# mpg-200-prototype_v3-with-logo-merged.net
KiCad netlist of a schematic drawn in EAGLE
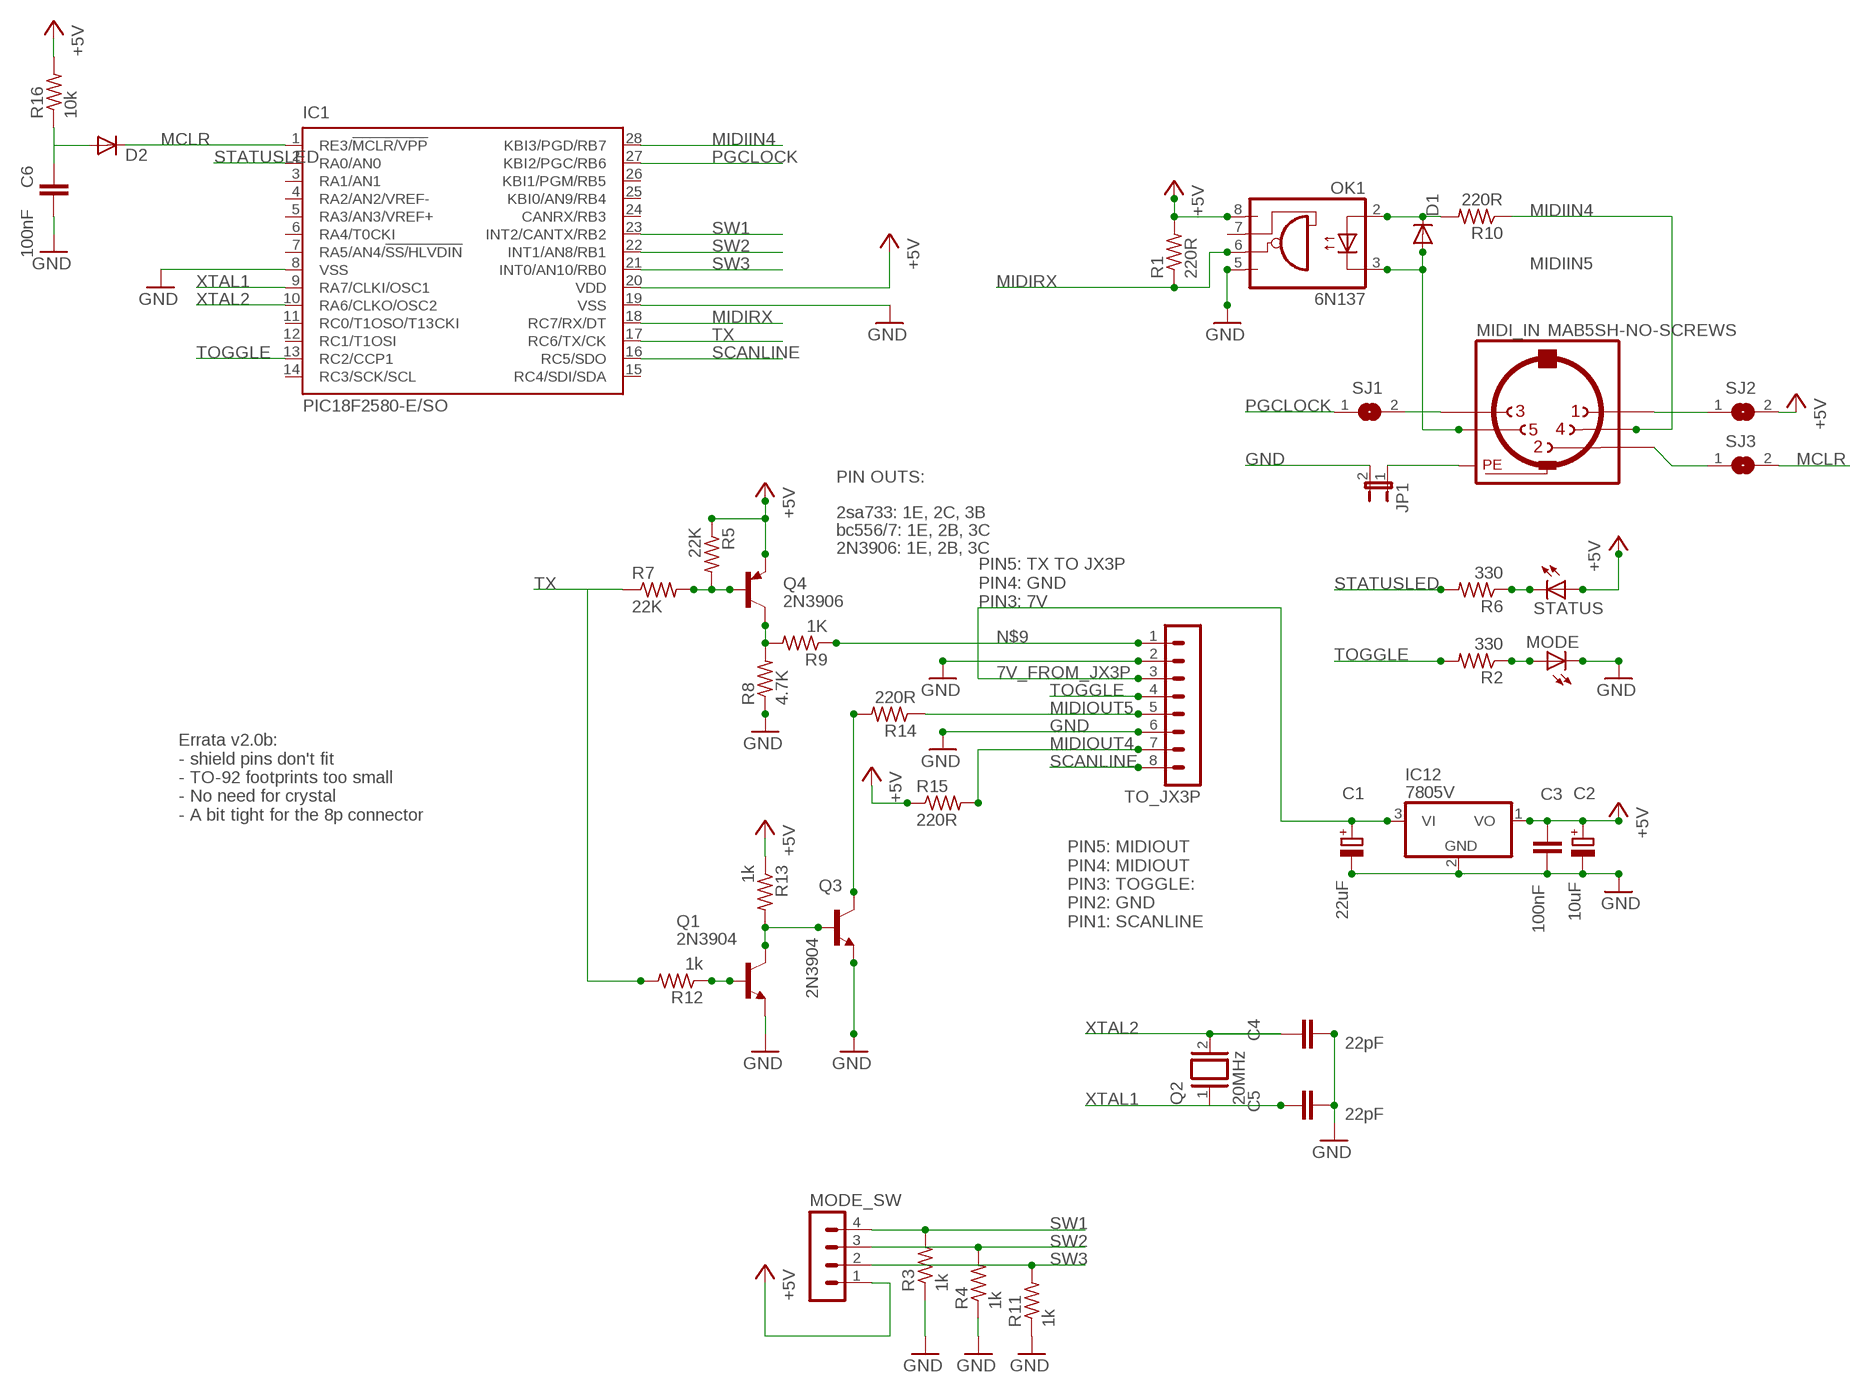
[diagram p0: schematic, sheet 1]

(export (version "E")
  (design (tool "Eeschema 10.0.6"))
  (components
    (comp (ref "C1")
      (value "22uF")
      (footprint "eagle-import:E2,5-5")
      (libsource (lib "eagle-import") (part "CPOL-EUE2.5-5"))
    )
    (comp (ref "C2")
      (value "10uF")
      (footprint "eagle-import:E2,5-5")
      (libsource (lib "eagle-import") (part "CPOL-EUE2.5-5"))
    )
    (comp (ref "C3")
      (value "100nF")
      (footprint "eagle-import:C0805")
      (libsource (lib "eagle-import") (part "C-EUC0805"))
    )
    (comp (ref "C4")
      (value "22pF")
      (footprint "eagle-import:C0805")
      (libsource (lib "eagle-import") (part "C-EUC0805"))
    )
    (comp (ref "C5")
      (value "22pF")
      (footprint "eagle-import:C0805")
      (libsource (lib "eagle-import") (part "C-EUC0805"))
    )
    (comp (ref "C6")
      (value "100nF")
      (footprint "eagle-import:C0805")
      (libsource (lib "eagle-import") (part "C-EUC0805"))
    )
    (comp (ref "D1")
      (value "DIODE-SOD80C")
      (footprint "eagle-import:SOD80C")
      (libsource (lib "eagle-import") (part "DIODE-SOD80C"))
    )
    (comp (ref "D2")
      (value "DIODE-SOD80C")
      (footprint "eagle-import:SOD80C")
      (libsource (lib "eagle-import") (part "DIODE-SOD80C"))
    )
    (comp (ref "IC1")
      (value "PIC18F2580-E/SO")
      (footprint "eagle-import:SO28W")
      (fields (field (name "MF") "MICROCHIP") (field (name "MPN") "PIC18F2580-I/SO"))
      (libsource (lib "eagle-import") (part "PIC18F280-E/SO5"))
    )
    (comp (ref "IC12")
      (value "7805V")
      (footprint "eagle-import:TO92")
      (libsource (lib "eagle-import") (part "78L05"))
    )
    (comp (ref "JP1")
      (value "JP1E")
      (footprint "eagle-import:JP1")
      (libsource (lib "eagle-import") (part "JP1E"))
    )
    (comp (ref "MIDI_IN")
      (value "MAB5SH-NO-SCREWS")
      (footprint "eagle-import:MAB5SH-NO-SCREWS")
      (libsource (lib "eagle-import") (part "MAB5SH-NO-SCREWS"))
    )
    (comp (ref "MODE")
      (value "LED3MM")
      (footprint "eagle-import:LED3MM")
      (libsource (lib "eagle-import") (part "LED3MM"))
    )
    (comp (ref "MODE_SW")
      (value "MA04-1")
      (footprint "eagle-import:MA04-1")
      (libsource (lib "eagle-import") (part "MA04-1"))
    )
    (comp (ref "OK1")
      (value "6N137")
      (footprint "eagle-import:DIL08")
      (libsource (lib "eagle-import") (part "6N137"))
    )
    (comp (ref "Q1")
      (value "2N3904")
      (footprint "eagle-import:TO92")
      (libsource (lib "eagle-import") (part "2N3904"))
    )
    (comp (ref "Q2")
      (value "20MHz")
      (footprint "eagle-import:QS")
      (libsource (lib "eagle-import") (part "XTAL/S"))
    )
    (comp (ref "Q3")
      (value "2N3904")
      (footprint "eagle-import:TO92")
      (libsource (lib "eagle-import") (part "2N3904"))
    )
    (comp (ref "Q4")
      (value "2N3906")
      (footprint "eagle-import:TO92")
      (libsource (lib "eagle-import") (part "2N3906"))
    )
    (comp (ref "R1")
      (value "220R")
      (footprint "eagle-import:R0805")
      (libsource (lib "eagle-import") (part "R-US_R0805"))
    )
    (comp (ref "R2")
      (value "330")
      (footprint "eagle-import:R0805")
      (libsource (lib "eagle-import") (part "R-US_R0805"))
    )
    (comp (ref "R3")
      (value "1k")
      (footprint "eagle-import:R0805")
      (libsource (lib "eagle-import") (part "R-US_R0805"))
    )
    (comp (ref "R4")
      (value "1k")
      (footprint "eagle-import:R0805")
      (libsource (lib "eagle-import") (part "R-US_R0805"))
    )
    (comp (ref "R5")
      (value "22K")
      (footprint "eagle-import:R0805")
      (libsource (lib "eagle-import") (part "R-US_R0805"))
    )
    (comp (ref "R6")
      (value "330")
      (footprint "eagle-import:R0805")
      (libsource (lib "eagle-import") (part "R-US_R0805"))
    )
    (comp (ref "R7")
      (value "22K")
      (footprint "eagle-import:R0805")
      (libsource (lib "eagle-import") (part "R-US_R0805"))
    )
    (comp (ref "R8")
      (value "4.7K")
      (footprint "eagle-import:R0805")
      (libsource (lib "eagle-import") (part "R-US_R0805"))
    )
    (comp (ref "R9")
      (value "1K")
      (footprint "eagle-import:R0805")
      (libsource (lib "eagle-import") (part "R-US_R0805"))
    )
    (comp (ref "R10")
      (value "220R")
      (footprint "eagle-import:R0805")
      (libsource (lib "eagle-import") (part "R-US_R0805"))
    )
    (comp (ref "R11")
      (value "1k")
      (footprint "eagle-import:R0805")
      (libsource (lib "eagle-import") (part "R-US_R0805"))
    )
    (comp (ref "R12")
      (value "1k")
      (footprint "eagle-import:R0805")
      (libsource (lib "eagle-import") (part "R-US_R0805"))
    )
    (comp (ref "R13")
      (value "1k")
      (footprint "eagle-import:R0805")
      (libsource (lib "eagle-import") (part "R-US_R0805"))
    )
    (comp (ref "R14")
      (value "220R")
      (footprint "eagle-import:R0805")
      (libsource (lib "eagle-import") (part "R-US_R0805"))
    )
    (comp (ref "R15")
      (value "220R")
      (footprint "eagle-import:R0805")
      (libsource (lib "eagle-import") (part "R-US_R0805"))
    )
    (comp (ref "R16")
      (value "10k")
      (footprint "eagle-import:R0805")
      (libsource (lib "eagle-import") (part "R-US_R0805"))
    )
    (comp (ref "SJ1") (value "SJ") (footprint "eagle-import:SJ") (libsource (lib "eagle-import") (part "SJ")))
    (comp (ref "SJ2") (value "SJ") (footprint "eagle-import:SJ") (libsource (lib "eagle-import") (part "SJ")))
    (comp (ref "SJ3") (value "SJ") (footprint "eagle-import:SJ") (libsource (lib "eagle-import") (part "SJ")))
    (comp (ref "STATUS")
      (value "LED3MM")
      (footprint "eagle-import:LED3MM")
      (libsource (lib "eagle-import") (part "LED3MM"))
    )
    (comp (ref "TO_JX3P")
      (value "MA08-1")
      (footprint "eagle-import:MA08-1")
      (libsource (lib "eagle-import") (part "MA08-1"))
    )
  )
  (nets
    (net (code "1") (name "+5V") (class "Default")
      (node (ref "C2") (pin "+") (pinfunction "+_+") (pintype "passive"))
      (node (ref "C3") (pin "1") (pinfunction "1_1") (pintype "passive"))
      (node (ref "IC1") (pin "20") (pinfunction "VDD_20") (pintype "power_in"))
      (node (ref "IC12") (pin "1") (pinfunction "VO_1") (pintype "passive"))
      (node (ref "MODE_SW") (pin "1") (pinfunction "1_1") (pintype "passive"))
      (node (ref "OK1") (pin "8") (pinfunction "VCC_8") (pintype "passive"))
      (node (ref "Q4") (pin "1") (pinfunction "E_1") (pintype "passive"))
      (node (ref "R1") (pin "2") (pinfunction "2_2") (pintype "passive"))
      (node (ref "R13") (pin "1") (pinfunction "1_1") (pintype "passive"))
      (node (ref "R15") (pin "1") (pinfunction "1_1") (pintype "passive"))
      (node (ref "R16") (pin "2") (pinfunction "2_2") (pintype "passive"))
      (node (ref "R5") (pin "1") (pinfunction "1_1") (pintype "passive"))
      (node (ref "SJ2") (pin "2") (pinfunction "2_2") (pintype "passive"))
      (node (ref "STATUS") (pin "A") (pinfunction "A_A") (pintype "passive"))
    )
    (net (code "2") (name "/7V_FROM_JX3P") (class "Default")
      (node (ref "C1") (pin "+") (pinfunction "+_+") (pintype "passive"))
      (node (ref "IC12") (pin "3") (pinfunction "VI_3") (pintype "input"))
      (node (ref "TO_JX3P") (pin "3") (pinfunction "3_3") (pintype "passive"))
    )
    (net (code "3") (name "/MCLR") (class "Default")
      (node (ref "D2") (pin "C") (pinfunction "C_C") (pintype "passive"))
      (node (ref "IC1") (pin "1") (pinfunction "RE3/~{MCLR/VPP}_1") (pintype "input"))
      (node (ref "SJ3") (pin "2") (pinfunction "2_2") (pintype "passive"))
    )
    (net (code "4") (name "/MIDIIN4") (class "Default")
      (node (ref "IC1") (pin "28") (pinfunction "KBI3/PGD/RB7_28") (pintype "bidirectional"))
      (node (ref "MIDI_IN") (pin "4") (pinfunction "4_4") (pintype "passive"))
      (node (ref "R10") (pin "1") (pinfunction "1_1") (pintype "passive"))
    )
    (net (code "5") (name "/MIDIIN5") (class "Default")
      (node (ref "D1") (pin "A") (pinfunction "A_A") (pintype "passive"))
      (node (ref "MIDI_IN") (pin "5") (pinfunction "5_5") (pintype "passive"))
      (node (ref "OK1") (pin "3") (pinfunction "C_3") (pintype "passive"))
    )
    (net (code "6") (name "/MIDIOUT4") (class "Default")
      (node (ref "R15") (pin "2") (pinfunction "2_2") (pintype "passive"))
      (node (ref "TO_JX3P") (pin "7") (pinfunction "7_7") (pintype "passive"))
    )
    (net (code "7") (name "/MIDIOUT5") (class "Default")
      (node (ref "R14") (pin "1") (pinfunction "1_1") (pintype "passive"))
      (node (ref "TO_JX3P") (pin "5") (pinfunction "5_5") (pintype "passive"))
    )
    (net (code "8") (name "/MIDIRX") (class "Default")
      (node (ref "IC1") (pin "18") (pinfunction "RC7/RX/DT_18") (pintype "bidirectional"))
      (node (ref "OK1") (pin "6") (pinfunction "VO_6") (pintype "passive"))
      (node (ref "R1") (pin "1") (pinfunction "1_1") (pintype "passive"))
    )
    (net (code "9") (name "/N$9") (class "Default")
      (node (ref "R9") (pin "1") (pinfunction "1_1") (pintype "passive"))
      (node (ref "TO_JX3P") (pin "1") (pinfunction "1_1") (pintype "passive"))
    )
    (net (code "10") (name "/PGCLOCK") (class "Default")
      (node (ref "IC1") (pin "27") (pinfunction "KBI2/PGC/RB6_27") (pintype "bidirectional"))
      (node (ref "SJ1") (pin "1") (pinfunction "1_1") (pintype "passive"))
    )
    (net (code "11") (name "/SCANLINE") (class "Default")
      (node (ref "IC1") (pin "16") (pinfunction "RC5/SDO_16") (pintype "bidirectional"))
      (node (ref "TO_JX3P") (pin "8") (pinfunction "8_8") (pintype "passive"))
    )
    (net (code "12") (name "/STATUSLED") (class "Default")
      (node (ref "IC1") (pin "2") (pinfunction "RA0/AN0_2") (pintype "bidirectional"))
      (node (ref "R6") (pin "2") (pinfunction "2_2") (pintype "passive"))
    )
    (net (code "13") (name "/SW1") (class "Default")
      (node (ref "IC1") (pin "23") (pinfunction "INT2/CANTX/RB2_23") (pintype "bidirectional"))
      (node (ref "MODE_SW") (pin "4") (pinfunction "4_4") (pintype "passive"))
      (node (ref "R3") (pin "2") (pinfunction "2_2") (pintype "passive"))
    )
    (net (code "14") (name "/SW2") (class "Default")
      (node (ref "IC1") (pin "22") (pinfunction "INT1/AN8/RB1_22") (pintype "bidirectional"))
      (node (ref "MODE_SW") (pin "3") (pinfunction "3_3") (pintype "passive"))
      (node (ref "R4") (pin "2") (pinfunction "2_2") (pintype "passive"))
    )
    (net (code "15") (name "/SW3") (class "Default")
      (node (ref "IC1") (pin "21") (pinfunction "INT0/AN10/RB0_21") (pintype "bidirectional"))
      (node (ref "MODE_SW") (pin "2") (pinfunction "2_2") (pintype "passive"))
      (node (ref "R11") (pin "2") (pinfunction "2_2") (pintype "passive"))
    )
    (net (code "16") (name "/TOGGLE") (class "Default")
      (node (ref "IC1") (pin "13") (pinfunction "RC2/CCP1_13") (pintype "bidirectional"))
      (node (ref "R2") (pin "2") (pinfunction "2_2") (pintype "passive"))
      (node (ref "TO_JX3P") (pin "4") (pinfunction "4_4") (pintype "passive"))
    )
    (net (code "17") (name "/TX") (class "Default")
      (node (ref "IC1") (pin "17") (pinfunction "RC6/TX/CK_17") (pintype "bidirectional"))
      (node (ref "R12") (pin "2") (pinfunction "2_2") (pintype "passive"))
      (node (ref "R7") (pin "1") (pinfunction "1_1") (pintype "passive"))
    )
    (net (code "18") (name "/XTAL1") (class "Default")
      (node (ref "C5") (pin "1") (pinfunction "1_1") (pintype "passive"))
      (node (ref "IC1") (pin "9") (pinfunction "RA7/CLKI/OSC1_9") (pintype "input"))
      (node (ref "Q2") (pin "1") (pinfunction "1_1") (pintype "passive"))
    )
    (net (code "19") (name "/XTAL2") (class "Default")
      (node (ref "C4") (pin "1") (pinfunction "1_1") (pintype "passive"))
      (node (ref "IC1") (pin "10") (pinfunction "RA6/CLKO/OSC2_10") (pintype "output"))
      (node (ref "Q2") (pin "2") (pinfunction "2_2") (pintype "passive"))
    )
    (net (code "20") (name "GND") (class "Default")
      (node (ref "C1") (pin "-") (pinfunction "-_-") (pintype "passive"))
      (node (ref "C2") (pin "-") (pinfunction "-_-") (pintype "passive"))
      (node (ref "C3") (pin "2") (pinfunction "2_2") (pintype "passive"))
      (node (ref "C4") (pin "2") (pinfunction "2_2") (pintype "passive"))
      (node (ref "C5") (pin "2") (pinfunction "2_2") (pintype "passive"))
      (node (ref "C6") (pin "2") (pinfunction "2_2") (pintype "passive"))
      (node (ref "IC1") (pin "19") (pinfunction "VSS_19") (pintype "power_in"))
      (node (ref "IC1") (pin "8") (pinfunction "VSS_8") (pintype "power_in"))
      (node (ref "IC12") (pin "2") (pinfunction "GND_2") (pintype "passive"))
      (node (ref "JP1") (pin "2") (pinfunction "2_2") (pintype "passive"))
      (node (ref "MODE") (pin "K") (pinfunction "C_K") (pintype "passive"))
      (node (ref "OK1") (pin "5") (pinfunction "GND_5") (pintype "passive"))
      (node (ref "Q1") (pin "1") (pinfunction "E_1") (pintype "passive"))
      (node (ref "Q3") (pin "1") (pinfunction "E_1") (pintype "passive"))
      (node (ref "R11") (pin "1") (pinfunction "1_1") (pintype "passive"))
      (node (ref "R3") (pin "1") (pinfunction "1_1") (pintype "passive"))
      (node (ref "R4") (pin "1") (pinfunction "1_1") (pintype "passive"))
      (node (ref "R8") (pin "1") (pinfunction "1_1") (pintype "passive"))
      (node (ref "TO_JX3P") (pin "2") (pinfunction "2_2") (pintype "passive"))
      (node (ref "TO_JX3P") (pin "6") (pinfunction "6_6") (pintype "passive"))
    )
    (net (code "21") (name "Net-(C6-Pad1)") (class "Default")
      (node (ref "C6") (pin "1") (pinfunction "1_1") (pintype "passive"))
      (node (ref "D2") (pin "A") (pinfunction "A_A") (pintype "passive"))
      (node (ref "R16") (pin "1") (pinfunction "1_1") (pintype "passive"))
    )
    (net (code "22") (name "Net-(JP1-Pad1)") (class "Default")
      (node (ref "JP1") (pin "1") (pinfunction "1_1") (pintype "passive"))
      (node (ref "MIDI_IN") (pin "PE") (pinfunction "PE_PE") (pintype "power_in"))
      (node (ref "MIDI_IN") (pin "PE@") (pinfunction "PE_PE@") (pintype "power_in"))
    )
    (net (code "23") (name "Net-(MIDI_IN-Pad1)") (class "Default")
      (node (ref "MIDI_IN") (pin "1") (pinfunction "1_1") (pintype "passive"))
      (node (ref "SJ2") (pin "1") (pinfunction "1_1") (pintype "passive"))
    )
    (net (code "24") (name "Net-(MIDI_IN-Pad2)") (class "Default")
      (node (ref "MIDI_IN") (pin "2") (pinfunction "2_2") (pintype "passive"))
      (node (ref "SJ3") (pin "1") (pinfunction "1_1") (pintype "passive"))
    )
    (net (code "25") (name "Net-(MIDI_IN-Pad3)") (class "Default")
      (node (ref "MIDI_IN") (pin "3") (pinfunction "3_3") (pintype "passive"))
      (node (ref "SJ1") (pin "2") (pinfunction "2_2") (pintype "passive"))
    )
    (net (code "26") (name "Net-(MODE-PadA)") (class "Default")
      (node (ref "MODE") (pin "A") (pinfunction "A_A") (pintype "passive"))
      (node (ref "R2") (pin "1") (pinfunction "1_1") (pintype "passive"))
    )
    (net (code "27") (name "Net-(OK1-A)") (class "Default")
      (node (ref "D1") (pin "C") (pinfunction "C_C") (pintype "passive"))
      (node (ref "OK1") (pin "2") (pinfunction "A_2") (pintype "passive"))
      (node (ref "R10") (pin "2") (pinfunction "2_2") (pintype "passive"))
    )
    (net (code "28") (name "Net-(Q1-B)") (class "Default")
      (node (ref "Q1") (pin "2") (pinfunction "B_2") (pintype "passive"))
      (node (ref "R12") (pin "1") (pinfunction "1_1") (pintype "passive"))
    )
    (net (code "29") (name "Net-(Q1-C)") (class "Default")
      (node (ref "Q1") (pin "3") (pinfunction "C_3") (pintype "passive"))
      (node (ref "Q3") (pin "2") (pinfunction "B_2") (pintype "passive"))
      (node (ref "R13") (pin "2") (pinfunction "2_2") (pintype "passive"))
    )
    (net (code "30") (name "Net-(Q3-C)") (class "Default")
      (node (ref "Q3") (pin "3") (pinfunction "C_3") (pintype "passive"))
      (node (ref "R14") (pin "2") (pinfunction "2_2") (pintype "passive"))
    )
    (net (code "31") (name "Net-(Q4-B)") (class "Default")
      (node (ref "Q4") (pin "2") (pinfunction "B_2") (pintype "passive"))
      (node (ref "R5") (pin "2") (pinfunction "2_2") (pintype "passive"))
      (node (ref "R7") (pin "2") (pinfunction "2_2") (pintype "passive"))
    )
    (net (code "32") (name "Net-(Q4-C)") (class "Default")
      (node (ref "Q4") (pin "3") (pinfunction "C_3") (pintype "passive"))
      (node (ref "R8") (pin "2") (pinfunction "2_2") (pintype "passive"))
      (node (ref "R9") (pin "2") (pinfunction "2_2") (pintype "passive"))
    )
    (net (code "33") (name "Net-(STATUS-C)") (class "Default")
      (node (ref "R6") (pin "1") (pinfunction "1_1") (pintype "passive"))
      (node (ref "STATUS") (pin "K") (pinfunction "C_K") (pintype "passive"))
    )
    (net (code "34") (name "unconnected-(IC1-CANRX{slash}RB3-Pad24)") (class "Default")
      (node (ref "IC1") (pin "24") (pinfunction "CANRX/RB3_24") (pintype "bidirectional"))
    )
    (net (code "35") (name "unconnected-(IC1-KBI0{slash}AN9{slash}RB4-Pad25)") (class "Default")
      (node (ref "IC1") (pin "25") (pinfunction "KBI0/AN9/RB4_25") (pintype "bidirectional"))
    )
    (net (code "36") (name "unconnected-(IC1-KBI1{slash}PGM{slash}RB5-Pad26)") (class "Default")
      (node (ref "IC1") (pin "26") (pinfunction "KBI1/PGM/RB5_26") (pintype "bidirectional"))
    )
    (net (code "37") (name "unconnected-(IC1-RA1{slash}AN1-Pad3)") (class "Default")
      (node (ref "IC1") (pin "3") (pinfunction "RA1/AN1_3") (pintype "bidirectional"))
    )
    (net (code "38") (name "unconnected-(IC1-RA2{slash}AN2{slash}VREF--Pad4)") (class "Default")
      (node (ref "IC1") (pin "4") (pinfunction "RA2/AN2/VREF-_4") (pintype "bidirectional"))
    )
    (net (code "39") (name "unconnected-(IC1-RA3{slash}AN3{slash}VREF+-Pad5)") (class "Default")
      (node (ref "IC1") (pin "5") (pinfunction "RA3/AN3/VREF+_5") (pintype "bidirectional"))
    )
    (net (code "40") (name "unconnected-(IC1-RA4{slash}T0CKI-Pad6)") (class "Default")
      (node (ref "IC1") (pin "6") (pinfunction "RA4/T0CKI_6") (pintype "bidirectional"))
    )
    (net (code "41") (name "unconnected-(IC1-RA5{slash}AN4{slash}~{SS{slash}HLVDIN}-Pad7)") (class "Default")
      (node (ref "IC1") (pin "7") (pinfunction "RA5/AN4/~{SS/HLVDIN}_7") (pintype "bidirectional"))
    )
    (net (code "42") (name "unconnected-(IC1-RC0{slash}T1OSO{slash}T13CKI-Pad11)") (class "Default")
      (node (ref "IC1") (pin "11") (pinfunction "RC0/T1OSO/T13CKI_11") (pintype "bidirectional"))
    )
    (net (code "43") (name "unconnected-(IC1-RC1{slash}T1OSI-Pad12)") (class "Default")
      (node (ref "IC1") (pin "12") (pinfunction "RC1/T1OSI_12") (pintype "bidirectional"))
    )
    (net (code "44") (name "unconnected-(IC1-RC3{slash}SCK{slash}SCL-Pad14)") (class "Default")
      (node (ref "IC1") (pin "14") (pinfunction "RC3/SCK/SCL_14") (pintype "bidirectional"))
    )
    (net (code "45") (name "unconnected-(IC1-RC4{slash}SDI{slash}SDA-Pad15)") (class "Default")
      (node (ref "IC1") (pin "15") (pinfunction "RC4/SDI/SDA_15") (pintype "bidirectional"))
    )
    (net (code "46") (name "unconnected-(OK1-VE-Pad7)") (class "Default")
      (node (ref "OK1") (pin "7") (pinfunction "VE_7") (pintype "passive"))
    )
  )
)
